# switch-smd-20mm-mk-2_1.net
KiCad netlist of a schematic drawn in EAGLE
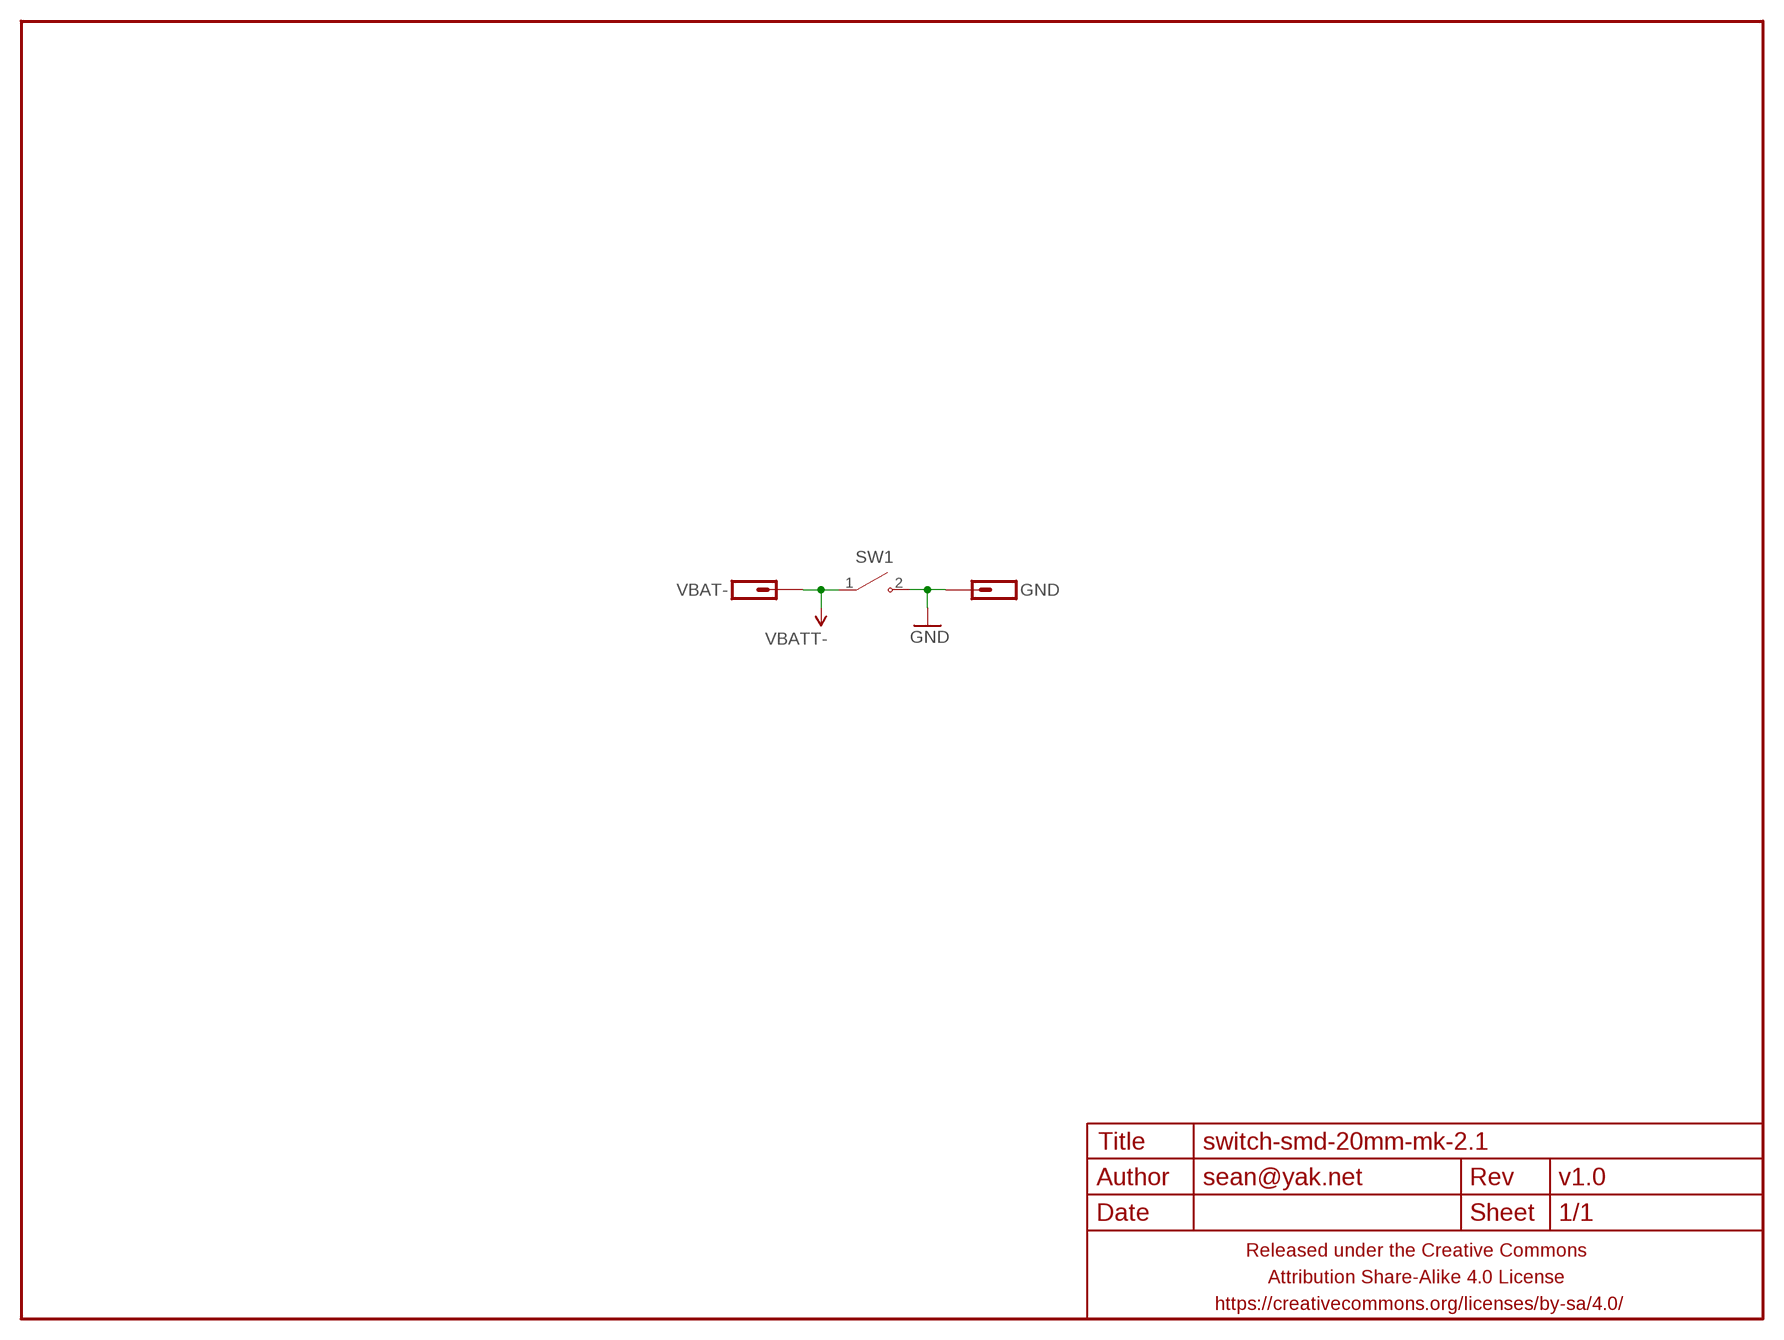
[diagram p0: schematic, sheet 1]

(export (version "E")
  (design (tool "Eeschema 10.0.6"))
  (components
    (comp (ref "FRAME1")
      (value "FRAME-LETTERNO_PACKAGE")
      (footprint "eagle-import:DUMMY")
      (fields (field (name "DESIGNER") "sean@yak.net") (field (name "VERSION") "v1.0"))
      (libsource (lib "eagle-import") (part "FRAME-LETTERNO_PACKAGE"))
    )
    (comp (ref "GND")
      (value "M01SMD_ANCHOR")
      (footprint "eagle-import:1X01_SMD_ANCHOR")
      (libsource (lib "eagle-import") (part "M01SMD_ANCHOR"))
    )
    (comp (ref "SW1")
      (value "SWITCH-SPSTKAN-9-PTH")
      (footprint "eagle-import:KAN-9")
      (libsource (lib "eagle-import") (part "SWITCH-SPSTKAN-9-PTH"))
    )
    (comp (ref "VBAT-")
      (value "M01PTH-1MM-CIR-NS")
      (footprint "eagle-import:1X01-1MM-CIR-NS")
      (libsource (lib "eagle-import") (part "M01PTH-1MM-CIR-NS"))
    )
  )
  (nets
    (net (code "1") (name "GND") (class "Default")
      (node (ref "GND") (pin "P$1") (pinfunction "1_P$1") (pintype "passive"))
      (node (ref "SW1") (pin "2") (pinfunction "NO_2") (pintype "bidirectional"))
    )
    (net (code "2") (name "VBATT-") (class "Default")
      (node (ref "SW1") (pin "1") (pinfunction "COM_1") (pintype "bidirectional"))
      (node (ref "VBAT-") (pin "1") (pinfunction "1_1") (pintype "passive"))
    )
  )
)
